# PAGE4_RELAYS.net
KiCad netlist of a schematic drawn in Altium Designer
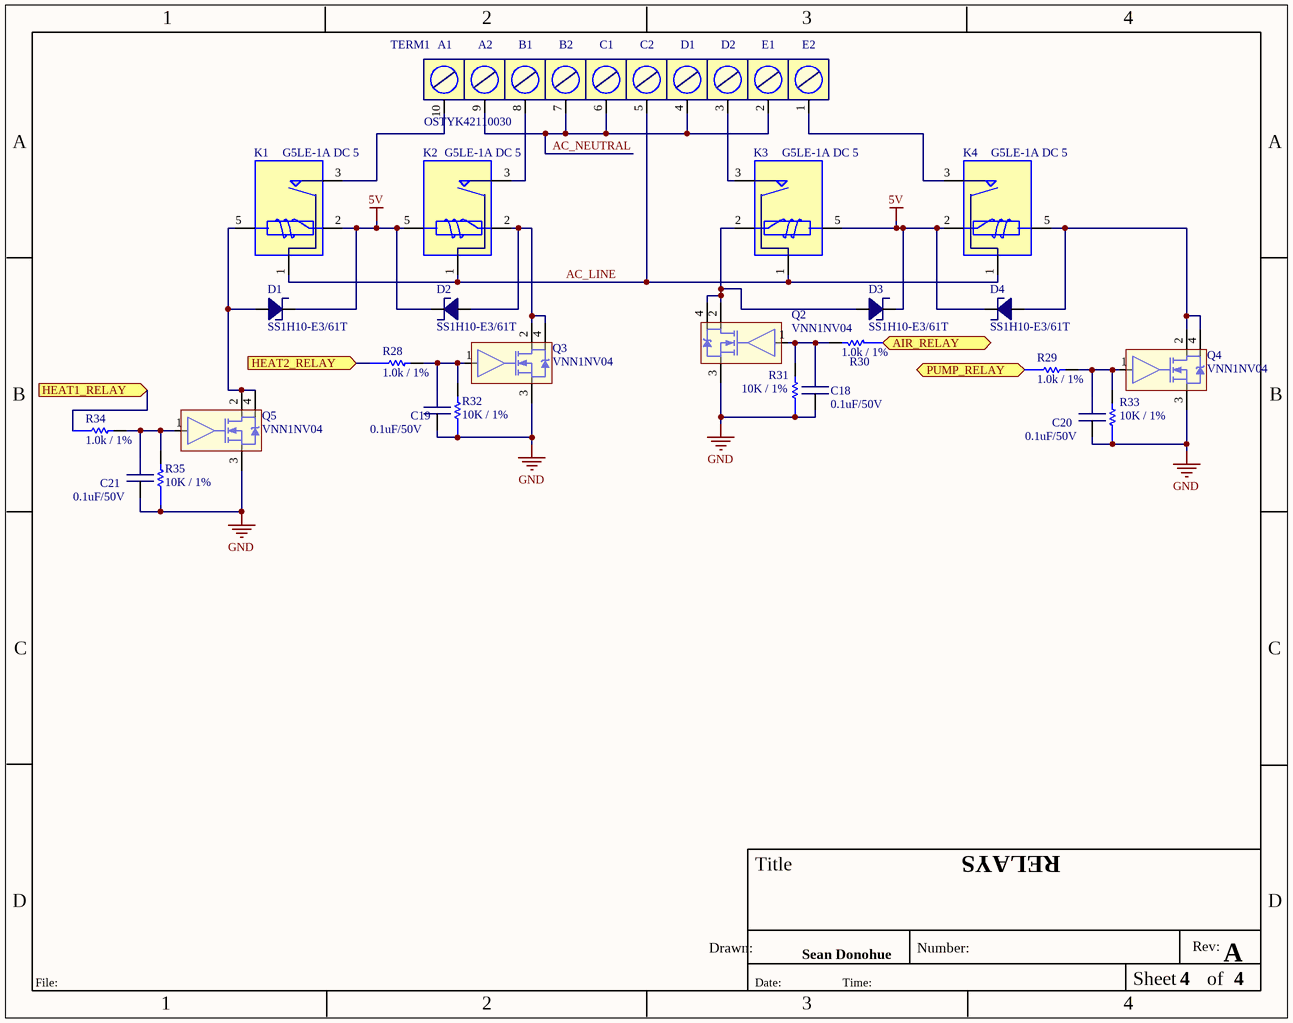
[diagram p0: PAGE4_RELAYS.SchDoc]

(export (version "E")
  (design (tool "Eeschema 10.0.6"))
  (components
    (comp (ref "C18")
      (value "0.1uF/50V")
      (footprint "0603")
      (description "CAP CER 0.1UF 50V 10% X7R 0603")
      (fields (field (name "MFG") "Murata") (field (name "Comment") "cap"))
      (libsource (lib "eetrex comp db") (part "cap"))
    )
    (comp (ref "C19")
      (value "0.1uF/50V")
      (footprint "0603")
      (description "CAP CER 0.1UF 50V 10% X7R 0603")
      (fields (field (name "MFG") "Murata") (field (name "Comment") "cap"))
      (libsource (lib "eetrex comp db") (part "cap"))
    )
    (comp (ref "C20")
      (value "0.1uF/50V")
      (footprint "0603")
      (description "CAP CER 0.1UF 50V 10% X7R 0603")
      (fields (field (name "MFG") "Murata") (field (name "Comment") "cap"))
      (libsource (lib "eetrex comp db") (part "cap"))
    )
    (comp (ref "C21")
      (value "0.1uF/50V")
      (footprint "0603")
      (description "CAP CER 0.1UF 50V 10% X7R 0603")
      (fields (field (name "MFG") "Murata") (field (name "Comment") "cap"))
      (libsource (lib "eetrex comp db") (part "cap"))
    )
    (comp (ref "D1")
      (value "SS1H10-E3/61T")
      (footprint "SMAZ")
      (description "DIODE SCHOTTKY 100V 1A DO214AC")
      (fields (field (name "MFG") "Vishay") (field (name "Comment") "ds"))
      (libsource (lib "eetrex comp db") (part "ds"))
    )
    (comp (ref "D2")
      (value "SS1H10-E3/61T")
      (footprint "SMAZ")
      (description "DIODE SCHOTTKY 100V 1A DO214AC")
      (fields (field (name "MFG") "Vishay") (field (name "Comment") "ds"))
      (libsource (lib "eetrex comp db") (part "ds"))
    )
    (comp (ref "D3")
      (value "SS1H10-E3/61T")
      (footprint "SMAZ")
      (description "DIODE SCHOTTKY 100V 1A DO214AC")
      (fields (field (name "MFG") "Vishay") (field (name "Comment") "ds"))
      (libsource (lib "eetrex comp db") (part "ds"))
    )
    (comp (ref "D4")
      (value "SS1H10-E3/61T")
      (footprint "SMAZ")
      (description "DIODE SCHOTTKY 100V 1A DO214AC")
      (fields (field (name "MFG") "Vishay") (field (name "Comment") "ds"))
      (libsource (lib "eetrex comp db") (part "ds"))
    )
    (comp (ref "K1")
      (value "G5LE-1A DC 5")
      (footprint "G5LE-SPST")
      (description "RELAY GEN PURPOSE SPST 16A 5V")
      (fields (field (name "MFG") "Omron") (field (name "Comment") "G5LE-SPST"))
      (libsource (lib "") (part "G5LE-SPST_1"))
    )
    (comp (ref "K2")
      (value "G5LE-1A DC 5")
      (footprint "G5LE-SPST")
      (description "RELAY GEN PURPOSE SPST 16A 5V")
      (fields (field (name "MFG") "Omron") (field (name "Comment") "G5LE-SPST"))
      (libsource (lib "") (part "G5LE-SPST_1"))
    )
    (comp (ref "K3")
      (value "G5LE-1A DC 5")
      (footprint "G5LE-SPST")
      (description "RELAY GEN PURPOSE SPST 16A 5V")
      (fields (field (name "MFG") "Omron") (field (name "Comment") "G5LE-SPST"))
      (libsource (lib "eetrex comp db") (part "G5LE-SPST"))
    )
    (comp (ref "K4")
      (value "G5LE-1A DC 5")
      (footprint "G5LE-SPST")
      (description "RELAY GEN PURPOSE SPST 16A 5V")
      (fields (field (name "MFG") "Omron") (field (name "Comment") "G5LE-SPST"))
      (libsource (lib "eetrex comp db") (part "G5LE-SPST"))
    )
    (comp (ref "Q2")
      (value "VNN1NV04")
      (footprint "SOT-223-4")
      (description "MOSFET N-CH 40V 1.7A SOT223")
      (fields (field (name "MFG") "ST Micro") (field (name "Comment") "NMOS-SOT-223-4"))
      (libsource (lib "eetrex comp db") (part "NMOS_Power_Omnifet2"))
    )
    (comp (ref "Q3")
      (value "VNN1NV04")
      (footprint "SOT-223-4")
      (description "MOSFET N-CH 40V 1.7A SOT223")
      (fields (field (name "MFG") "ST Micro") (field (name "Comment") "NMOS-SOT-223-4"))
      (libsource (lib "") (part "NMOS_Power_Omnifet2_1"))
    )
    (comp (ref "Q4")
      (value "VNN1NV04")
      (footprint "SOT-223-4")
      (description "MOSFET N-CH 40V 1.7A SOT223")
      (fields (field (name "MFG") "ST Micro") (field (name "Comment") "NMOS-SOT-223-4"))
      (libsource (lib "") (part "NMOS_Power_Omnifet2_1"))
    )
    (comp (ref "Q5")
      (value "VNN1NV04")
      (footprint "SOT-223-4")
      (description "MOSFET N-CH 40V 1.7A SOT223")
      (fields (field (name "MFG") "ST Micro") (field (name "Comment") "NMOS-SOT-223-4"))
      (libsource (lib "") (part "NMOS_Power_Omnifet2_1"))
    )
    (comp (ref "R28")
      (value "1.0k / 1%")
      (footprint "0603")
      (description "RES 1.00K OHM 1/10W 1% 0603 SMD")
      (fields (field (name "MFG") "Vishay") (field (name "Comment") "Res"))
      (libsource (lib "eetrex comp db") (part "Res"))
    )
    (comp (ref "R29")
      (value "1.0k / 1%")
      (footprint "0603")
      (description "RES 1.00K OHM 1/10W 1% 0603 SMD")
      (fields (field (name "MFG") "Vishay") (field (name "Comment") "Res"))
      (libsource (lib "eetrex comp db") (part "Res"))
    )
    (comp (ref "R30")
      (value "1.0k / 1%")
      (footprint "0603")
      (description "RES 1.00K OHM 1/10W 1% 0603 SMD")
      (fields (field (name "MFG") "Vishay") (field (name "Comment") "Res"))
      (libsource (lib "eetrex comp db") (part "Res"))
    )
    (comp (ref "R31")
      (value "10K / 1%")
      (footprint "0603")
      (description "RES 10K OHM 1% 1/8W 0603 SMD")
      (fields (field (name "MFG") "Vishay") (field (name "Comment") "Res"))
      (libsource (lib "eetrex comp db") (part "Res"))
    )
    (comp (ref "R32")
      (value "10K / 1%")
      (footprint "0603")
      (description "RES 10K OHM 1% 1/8W 0603 SMD")
      (fields (field (name "MFG") "Vishay") (field (name "Comment") "Res"))
      (libsource (lib "eetrex comp db") (part "Res"))
    )
    (comp (ref "R33")
      (value "10K / 1%")
      (footprint "0603")
      (description "RES 10K OHM 1% 1/8W 0603 SMD")
      (fields (field (name "MFG") "Vishay") (field (name "Comment") "Res"))
      (libsource (lib "eetrex comp db") (part "Res"))
    )
    (comp (ref "R34")
      (value "1.0k / 1%")
      (footprint "0603")
      (description "RES 1.00K OHM 1/10W 1% 0603 SMD")
      (fields (field (name "MFG") "Vishay") (field (name "Comment") "Res"))
      (libsource (lib "eetrex comp db") (part "Res"))
    )
    (comp (ref "R35")
      (value "10K / 1%")
      (footprint "0603")
      (description "RES 10K OHM 1% 1/8W 0603 SMD")
      (fields (field (name "MFG") "Vishay") (field (name "Comment") "Res"))
      (libsource (lib "eetrex comp db") (part "Res"))
    )
    (comp (ref "TERM1")
      (value "OSTYK42110030")
      (footprint "BARRIER-STRP-10")
      (description "CONN BARRIER STRP 10CIRC 0.325\"")
      (fields (field (name "MFG") "On Shore Technology, Inc.") (field (name "Comment") "BARR-STRP-10"))
      (libsource (lib "eetrex comp db") (part "BARR-STRP-10"))
    )
  )
  (nets
    (net (code "1") (name "/AC_LINE") (class "Default")
      (node (ref "K1") (pin "1") (pinfunction "1_1") (pintype "passive"))
      (node (ref "K2") (pin "1") (pinfunction "1_1") (pintype "passive"))
      (node (ref "K3") (pin "1") (pinfunction "1_1") (pintype "passive"))
      (node (ref "K4") (pin "1") (pinfunction "1_1") (pintype "passive"))
      (node (ref "TERM1") (pin "5") (pinfunction "5_5") (pintype "passive"))
    )
    (net (code "2") (name "/AC_NEUTRAL") (class "Default")
      (node (ref "TERM1") (pin "2") (pinfunction "2_2") (pintype "passive"))
      (node (ref "TERM1") (pin "4") (pinfunction "4_4") (pintype "passive"))
      (node (ref "TERM1") (pin "6") (pinfunction "6_6") (pintype "passive"))
      (node (ref "TERM1") (pin "7") (pinfunction "7_7") (pintype "passive"))
      (node (ref "TERM1") (pin "9") (pinfunction "9_9") (pintype "passive"))
    )
    (net (code "3") (name "/AIR_RELAY") (class "Default")
      (node (ref "R30") (pin "1") (pinfunction "1_1") (pintype "passive"))
    )
    (net (code "4") (name "/HEAT1_RELAY") (class "Default")
      (node (ref "R34") (pin "1") (pinfunction "1_1") (pintype "passive"))
    )
    (net (code "5") (name "/HEAT2_RELAY") (class "Default")
      (node (ref "R28") (pin "1") (pinfunction "1_1") (pintype "passive"))
    )
    (net (code "6") (name "/PUMP_RELAY") (class "Default")
      (node (ref "R29") (pin "1") (pinfunction "1_1") (pintype "passive"))
    )
    (net (code "7") (name "5V") (class "Default")
      (node (ref "D1") (pin "1") (pinfunction "C_1") (pintype "passive"))
      (node (ref "D2") (pin "1") (pinfunction "C_1") (pintype "passive"))
      (node (ref "D3") (pin "1") (pinfunction "C_1") (pintype "passive"))
      (node (ref "D4") (pin "1") (pinfunction "C_1") (pintype "passive"))
      (node (ref "K1") (pin "2") (pinfunction "2_2") (pintype "passive"))
      (node (ref "K2") (pin "5") (pinfunction "5_5") (pintype "passive"))
      (node (ref "K3") (pin "5") (pinfunction "5_5") (pintype "passive"))
      (node (ref "K4") (pin "2") (pinfunction "2_2") (pintype "passive"))
    )
    (net (code "8") (name "GND") (class "Default")
      (node (ref "C18") (pin "2") (pinfunction "2_2") (pintype "passive"))
      (node (ref "C19") (pin "2") (pinfunction "2_2") (pintype "passive"))
      (node (ref "C20") (pin "2") (pinfunction "2_2") (pintype "passive"))
      (node (ref "C21") (pin "2") (pinfunction "2_2") (pintype "passive"))
      (node (ref "Q2") (pin "3") (pinfunction "S_3") (pintype "passive"))
      (node (ref "Q3") (pin "3") (pinfunction "S_3") (pintype "passive"))
      (node (ref "Q4") (pin "3") (pinfunction "S_3") (pintype "passive"))
      (node (ref "Q5") (pin "3") (pinfunction "S_3") (pintype "passive"))
      (node (ref "R31") (pin "1") (pinfunction "1_1") (pintype "passive"))
      (node (ref "R32") (pin "1") (pinfunction "1_1") (pintype "passive"))
      (node (ref "R33") (pin "1") (pinfunction "1_1") (pintype "passive"))
      (node (ref "R35") (pin "1") (pinfunction "1_1") (pintype "passive"))
    )
    (net (code "9") (name "Net-(D1-A)") (class "Default")
      (node (ref "D1") (pin "2") (pinfunction "A_2") (pintype "passive"))
      (node (ref "K1") (pin "5") (pinfunction "5_5") (pintype "passive"))
      (node (ref "Q5") (pin "2") (pinfunction "D_2") (pintype "passive"))
      (node (ref "Q5") (pin "4") (pinfunction "D_4") (pintype "passive"))
    )
    (net (code "10") (name "Net-(D2-A)") (class "Default")
      (node (ref "D2") (pin "2") (pinfunction "A_2") (pintype "passive"))
      (node (ref "K2") (pin "2") (pinfunction "2_2") (pintype "passive"))
      (node (ref "Q3") (pin "2") (pinfunction "D_2") (pintype "passive"))
      (node (ref "Q3") (pin "4") (pinfunction "D_4") (pintype "passive"))
    )
    (net (code "11") (name "Net-(D3-A)") (class "Default")
      (node (ref "D3") (pin "2") (pinfunction "A_2") (pintype "passive"))
      (node (ref "K3") (pin "2") (pinfunction "2_2") (pintype "passive"))
      (node (ref "Q2") (pin "2") (pinfunction "D_2") (pintype "passive"))
      (node (ref "Q2") (pin "4") (pinfunction "D_4") (pintype "passive"))
    )
    (net (code "12") (name "Net-(D4-A)") (class "Default")
      (node (ref "D4") (pin "2") (pinfunction "A_2") (pintype "passive"))
      (node (ref "K4") (pin "5") (pinfunction "5_5") (pintype "passive"))
      (node (ref "Q4") (pin "2") (pinfunction "D_2") (pintype "passive"))
      (node (ref "Q4") (pin "4") (pinfunction "D_4") (pintype "passive"))
    )
    (net (code "13") (name "Net-(K1-Pad3)") (class "Default")
      (node (ref "K1") (pin "3") (pinfunction "3_3") (pintype "passive"))
      (node (ref "TERM1") (pin "10") (pinfunction "10_10") (pintype "passive"))
    )
    (net (code "14") (name "Net-(K2-Pad3)") (class "Default")
      (node (ref "K2") (pin "3") (pinfunction "3_3") (pintype "passive"))
      (node (ref "TERM1") (pin "8") (pinfunction "8_8") (pintype "passive"))
    )
    (net (code "15") (name "Net-(K3-Pad3)") (class "Default")
      (node (ref "K3") (pin "3") (pinfunction "3_3") (pintype "passive"))
      (node (ref "TERM1") (pin "3") (pinfunction "3_3") (pintype "passive"))
    )
    (net (code "16") (name "Net-(K4-Pad3)") (class "Default")
      (node (ref "K4") (pin "3") (pinfunction "3_3") (pintype "passive"))
      (node (ref "TERM1") (pin "1") (pinfunction "1_1") (pintype "passive"))
    )
    (net (code "17") (name "Net-(Q2-G)") (class "Default")
      (node (ref "C18") (pin "1") (pinfunction "1_1") (pintype "passive"))
      (node (ref "Q2") (pin "1") (pinfunction "G_1") (pintype "passive"))
      (node (ref "R30") (pin "2") (pinfunction "2_2") (pintype "passive"))
      (node (ref "R31") (pin "2") (pinfunction "2_2") (pintype "passive"))
    )
    (net (code "18") (name "Net-(Q3-G)") (class "Default")
      (node (ref "C19") (pin "1") (pinfunction "1_1") (pintype "passive"))
      (node (ref "Q3") (pin "1") (pinfunction "G_1") (pintype "passive"))
      (node (ref "R28") (pin "2") (pinfunction "2_2") (pintype "passive"))
      (node (ref "R32") (pin "2") (pinfunction "2_2") (pintype "passive"))
    )
    (net (code "19") (name "Net-(Q4-G)") (class "Default")
      (node (ref "C20") (pin "1") (pinfunction "1_1") (pintype "passive"))
      (node (ref "Q4") (pin "1") (pinfunction "G_1") (pintype "passive"))
      (node (ref "R29") (pin "2") (pinfunction "2_2") (pintype "passive"))
      (node (ref "R33") (pin "2") (pinfunction "2_2") (pintype "passive"))
    )
    (net (code "20") (name "Net-(Q5-G)") (class "Default")
      (node (ref "C21") (pin "1") (pinfunction "1_1") (pintype "passive"))
      (node (ref "Q5") (pin "1") (pinfunction "G_1") (pintype "passive"))
      (node (ref "R34") (pin "2") (pinfunction "2_2") (pintype "passive"))
      (node (ref "R35") (pin "2") (pinfunction "2_2") (pintype "passive"))
    )
  )
)
